# temp_sensor.net
KiCad netlist of a schematic drawn in EAGLE
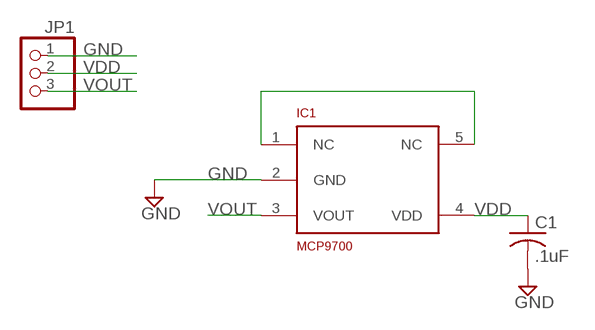
[diagram p0: schematic, sheet 1]

(export (version "E")
  (design (tool "Eeschema 10.0.6"))
  (components
    (comp (ref "C1")
      (value ".1uF")
      (footprint "eagle-import:C0805K")
      (libsource (lib "eagle-import") (part "C-USC0805K"))
    )
    (comp (ref "IC1")
      (value "MCP9700")
      (footprint "eagle-import:SC70")
      (libsource (lib "eagle-import") (part "MCP9700"))
    )
    (comp (ref "JP1")
      (value "PINHD-1X3")
      (footprint "eagle-import:1X03")
      (libsource (lib "eagle-import") (part "PINHD-1X3"))
    )
  )
  (nets
    (net (code "1") (name "/VDD") (class "Default")
      (node (ref "C1") (pin "1") (pinfunction "1_1") (pintype "passive"))
      (node (ref "IC1") (pin "4") (pinfunction "VDD_4") (pintype "bidirectional"))
      (node (ref "JP1") (pin "2") (pinfunction "2_2") (pintype "passive"))
    )
    (net (code "2") (name "/VOUT") (class "Default")
      (node (ref "IC1") (pin "3") (pinfunction "VOUT_3") (pintype "bidirectional"))
      (node (ref "JP1") (pin "3") (pinfunction "3_3") (pintype "passive"))
    )
    (net (code "3") (name "GND") (class "Default")
      (node (ref "C1") (pin "2") (pinfunction "2_2") (pintype "passive"))
      (node (ref "IC1") (pin "2") (pinfunction "GND_2") (pintype "bidirectional"))
      (node (ref "JP1") (pin "1") (pinfunction "1_1") (pintype "passive"))
    )
    (net (code "4") (name "Net-(IC1-NC-Pad1)") (class "Default")
      (node (ref "IC1") (pin "1") (pinfunction "NC_1") (pintype "bidirectional"))
      (node (ref "IC1") (pin "5") (pinfunction "NC_5") (pintype "bidirectional"))
    )
  )
)
